# question_4.net
KiCad netlist of a schematic drawn in EAGLE
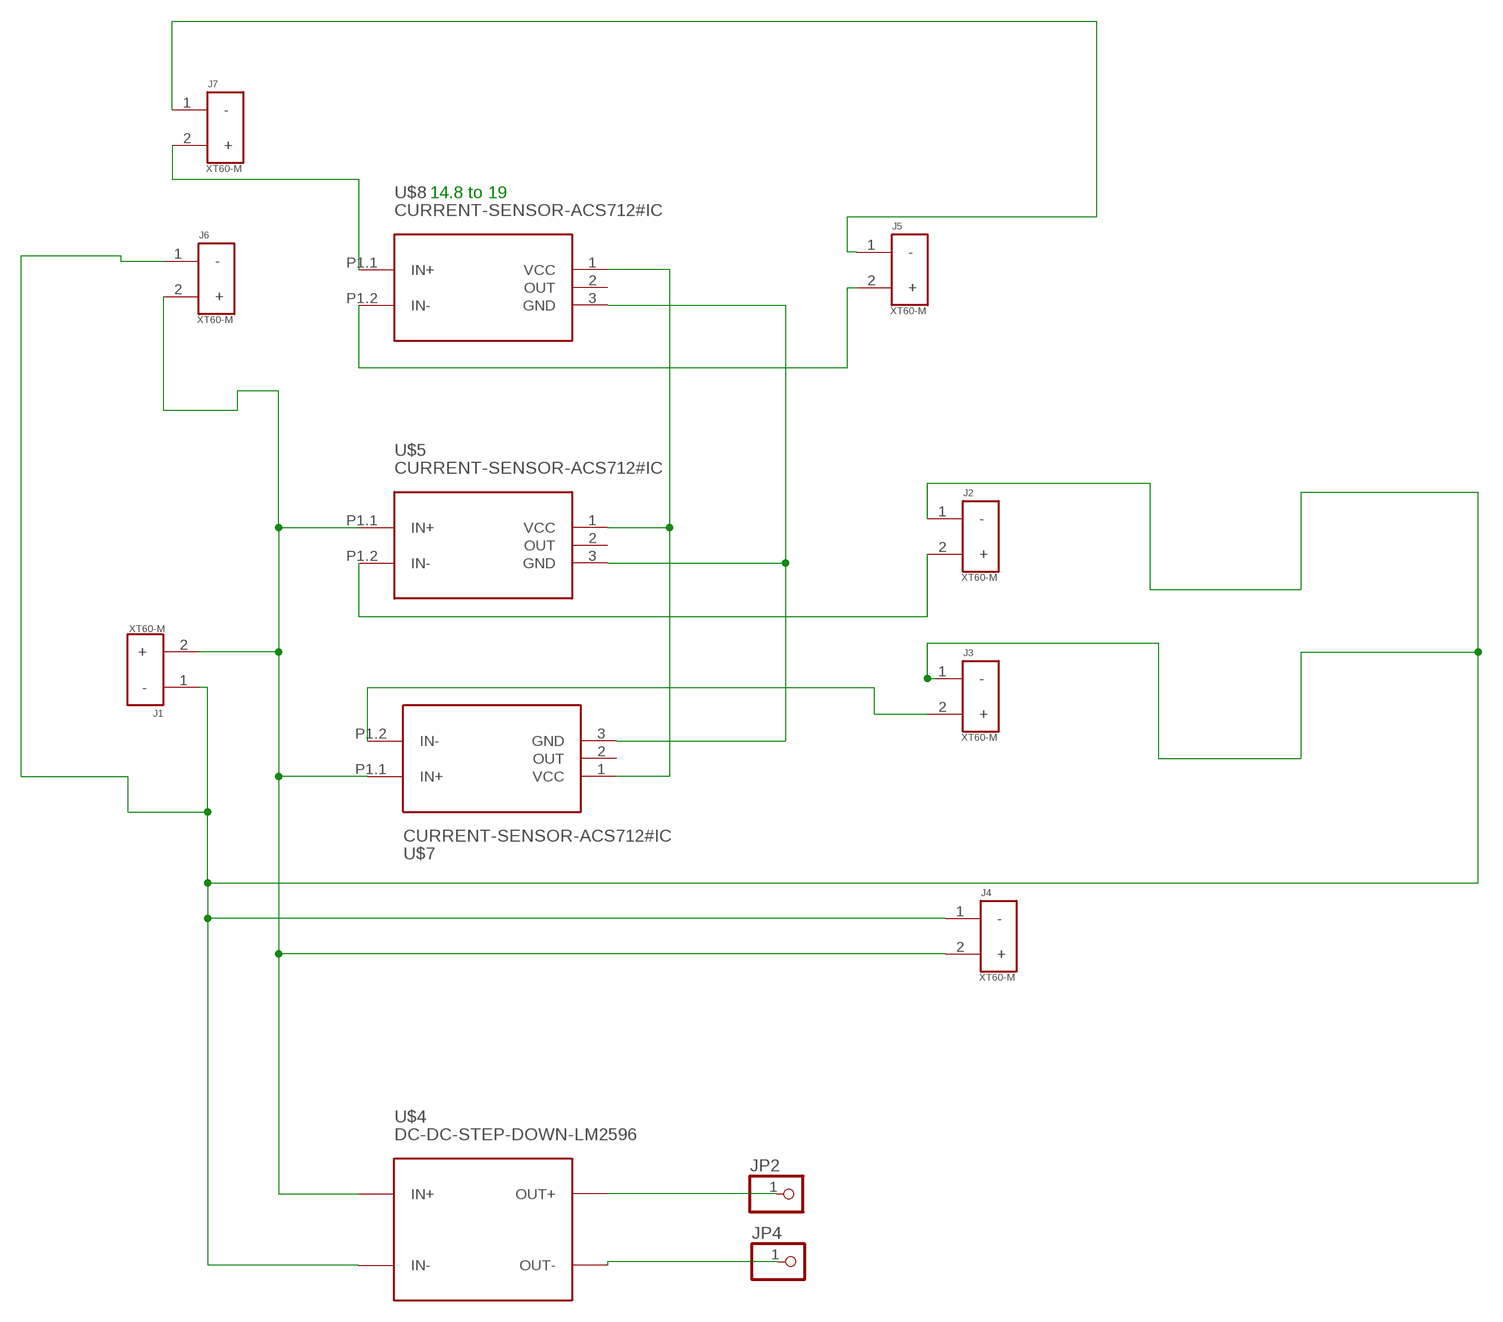
[diagram p0: schematic, sheet 1]

(export (version "E")
  (design (tool "Eeschema 10.0.6"))
  (components
    (comp (ref "J1")
      (value "XT60-M")
      (footprint "eagle-import:AMASS_XT60-M")
      (fields (field (name "MF") "AMASS"))
      (libsource (lib "eagle-import") (part "XT60-M"))
    )
    (comp (ref "J2")
      (value "XT60-M")
      (footprint "eagle-import:AMASS_XT60-M")
      (fields (field (name "MF") "AMASS"))
      (libsource (lib "eagle-import") (part "XT60-M"))
    )
    (comp (ref "J3")
      (value "XT60-M")
      (footprint "eagle-import:AMASS_XT60-M")
      (fields (field (name "MF") "AMASS"))
      (libsource (lib "eagle-import") (part "XT60-M"))
    )
    (comp (ref "J4")
      (value "XT60-M")
      (footprint "eagle-import:AMASS_XT60-M")
      (fields (field (name "MF") "AMASS"))
      (libsource (lib "eagle-import") (part "XT60-M"))
    )
    (comp (ref "J5")
      (value "XT60-M")
      (footprint "eagle-import:AMASS_XT60-M")
      (fields (field (name "MF") "AMASS"))
      (libsource (lib "eagle-import") (part "XT60-M"))
    )
    (comp (ref "J6")
      (value "XT60-M")
      (footprint "eagle-import:AMASS_XT60-M")
      (fields (field (name "MF") "AMASS"))
      (libsource (lib "eagle-import") (part "XT60-M"))
    )
    (comp (ref "J7")
      (value "XT60-M")
      (footprint "eagle-import:AMASS_XT60-M")
      (fields (field (name "MF") "AMASS"))
      (libsource (lib "eagle-import") (part "XT60-M"))
    )
    (comp (ref "JP2")
      (value "PINHD-1X1")
      (footprint "eagle-import:1X01")
      (libsource (lib "eagle-import") (part "PINHD-1X1"))
    )
    (comp (ref "JP4")
      (value "PINHD-1X1")
      (footprint "eagle-import:1X01")
      (libsource (lib "eagle-import") (part "PINHD-1X1"))
    )
    (comp (ref "U$4")
      (value "DC-DC-STEP-DOWN-LM2596")
      (footprint "eagle-import:DC-DC-STEP-DOWN-LM2596")
      (libsource (lib "eagle-import") (part "DC-DC-STEP-DOWN-LM2596"))
    )
    (comp (ref "U$5")
      (value "CURRENT-SENSOR-ACS712#IC")
      (footprint "eagle-import:CURRENT-SENSOR-ACS712#IC")
      (libsource (lib "eagle-import") (part "CURRENT-SENSOR-ACS712#IC"))
    )
    (comp (ref "U$7")
      (value "CURRENT-SENSOR-ACS712#IC")
      (footprint "eagle-import:CURRENT-SENSOR-ACS712#IC")
      (libsource (lib "eagle-import") (part "CURRENT-SENSOR-ACS712#IC"))
    )
    (comp (ref "U$8")
      (value "CURRENT-SENSOR-ACS712#IC")
      (footprint "eagle-import:CURRENT-SENSOR-ACS712#IC")
      (libsource (lib "eagle-import") (part "CURRENT-SENSOR-ACS712#IC"))
    )
  )
  (nets
    (net (code "1") (name "Net-(J1-+)") (class "Default")
      (node (ref "J1") (pin "2") (pinfunction "+_2") (pintype "passive"))
      (node (ref "J4") (pin "2") (pinfunction "+_2") (pintype "passive"))
      (node (ref "J6") (pin "2") (pinfunction "+_2") (pintype "passive"))
      (node (ref "U$4") (pin "IN+") (pinfunction "IN+_IN+") (pintype "bidirectional"))
      (node (ref "U$5") (pin "P1.1") (pinfunction "IN+_P1.1") (pintype "bidirectional"))
      (node (ref "U$7") (pin "P1.1") (pinfunction "IN+_P1.1") (pintype "bidirectional"))
    )
    (net (code "2") (name "Net-(J1--)") (class "Default")
      (node (ref "J1") (pin "1") (pinfunction "-_1") (pintype "passive"))
      (node (ref "J2") (pin "1") (pinfunction "-_1") (pintype "passive"))
      (node (ref "J3") (pin "1") (pinfunction "-_1") (pintype "passive"))
      (node (ref "J4") (pin "1") (pinfunction "-_1") (pintype "passive"))
      (node (ref "J6") (pin "1") (pinfunction "-_1") (pintype "passive"))
      (node (ref "U$4") (pin "IN-") (pinfunction "IN-_IN-") (pintype "bidirectional"))
    )
    (net (code "3") (name "Net-(J2-+)") (class "Default")
      (node (ref "J2") (pin "2") (pinfunction "+_2") (pintype "passive"))
      (node (ref "U$5") (pin "P1.2") (pinfunction "IN-_P1.2") (pintype "bidirectional"))
    )
    (net (code "4") (name "Net-(J3-+)") (class "Default")
      (node (ref "J3") (pin "2") (pinfunction "+_2") (pintype "passive"))
      (node (ref "U$7") (pin "P1.2") (pinfunction "IN-_P1.2") (pintype "bidirectional"))
    )
    (net (code "5") (name "Net-(J5-+)") (class "Default")
      (node (ref "J5") (pin "2") (pinfunction "+_2") (pintype "passive"))
      (node (ref "U$8") (pin "P1.2") (pinfunction "IN-_P1.2") (pintype "bidirectional"))
    )
    (net (code "6") (name "Net-(J5--)") (class "Default")
      (node (ref "J5") (pin "1") (pinfunction "-_1") (pintype "passive"))
      (node (ref "J7") (pin "1") (pinfunction "-_1") (pintype "passive"))
    )
    (net (code "7") (name "Net-(J7-+)") (class "Default")
      (node (ref "J7") (pin "2") (pinfunction "+_2") (pintype "passive"))
      (node (ref "U$8") (pin "P1.1") (pinfunction "IN+_P1.1") (pintype "bidirectional"))
    )
    (net (code "8") (name "Net-(JP2-Pad1)") (class "Default")
      (node (ref "JP2") (pin "1") (pinfunction "1_1") (pintype "passive"))
      (node (ref "U$4") (pin "OUT+") (pinfunction "OUT+_OUT+") (pintype "bidirectional"))
    )
    (net (code "9") (name "Net-(JP4-Pad1)") (class "Default")
      (node (ref "JP4") (pin "1") (pinfunction "1_1") (pintype "passive"))
      (node (ref "U$4") (pin "OUT-") (pinfunction "OUT-_OUT-") (pintype "bidirectional"))
    )
    (net (code "10") (name "Net-(U$5-GND)") (class "Default")
      (node (ref "U$5") (pin "3") (pinfunction "GND_3") (pintype "power_in"))
      (node (ref "U$7") (pin "3") (pinfunction "GND_3") (pintype "power_in"))
      (node (ref "U$8") (pin "3") (pinfunction "GND_3") (pintype "power_in"))
    )
    (net (code "11") (name "Net-(U$5-VCC)") (class "Default")
      (node (ref "U$5") (pin "1") (pinfunction "VCC_1") (pintype "power_in"))
      (node (ref "U$7") (pin "1") (pinfunction "VCC_1") (pintype "power_in"))
      (node (ref "U$8") (pin "1") (pinfunction "VCC_1") (pintype "power_in"))
    )
    (net (code "12") (name "unconnected-(U$5-OUT-Pad2)") (class "Default")
      (node (ref "U$5") (pin "2") (pinfunction "OUT_2") (pintype "output"))
    )
    (net (code "13") (name "unconnected-(U$7-OUT-Pad2)") (class "Default")
      (node (ref "U$7") (pin "2") (pinfunction "OUT_2") (pintype "output"))
    )
    (net (code "14") (name "unconnected-(U$8-OUT-Pad2)") (class "Default")
      (node (ref "U$8") (pin "2") (pinfunction "OUT_2") (pintype "output"))
    )
  )
)
